# nRF52840_qfaa_var5.net
KiCad netlist of a schematic drawn in EAGLE
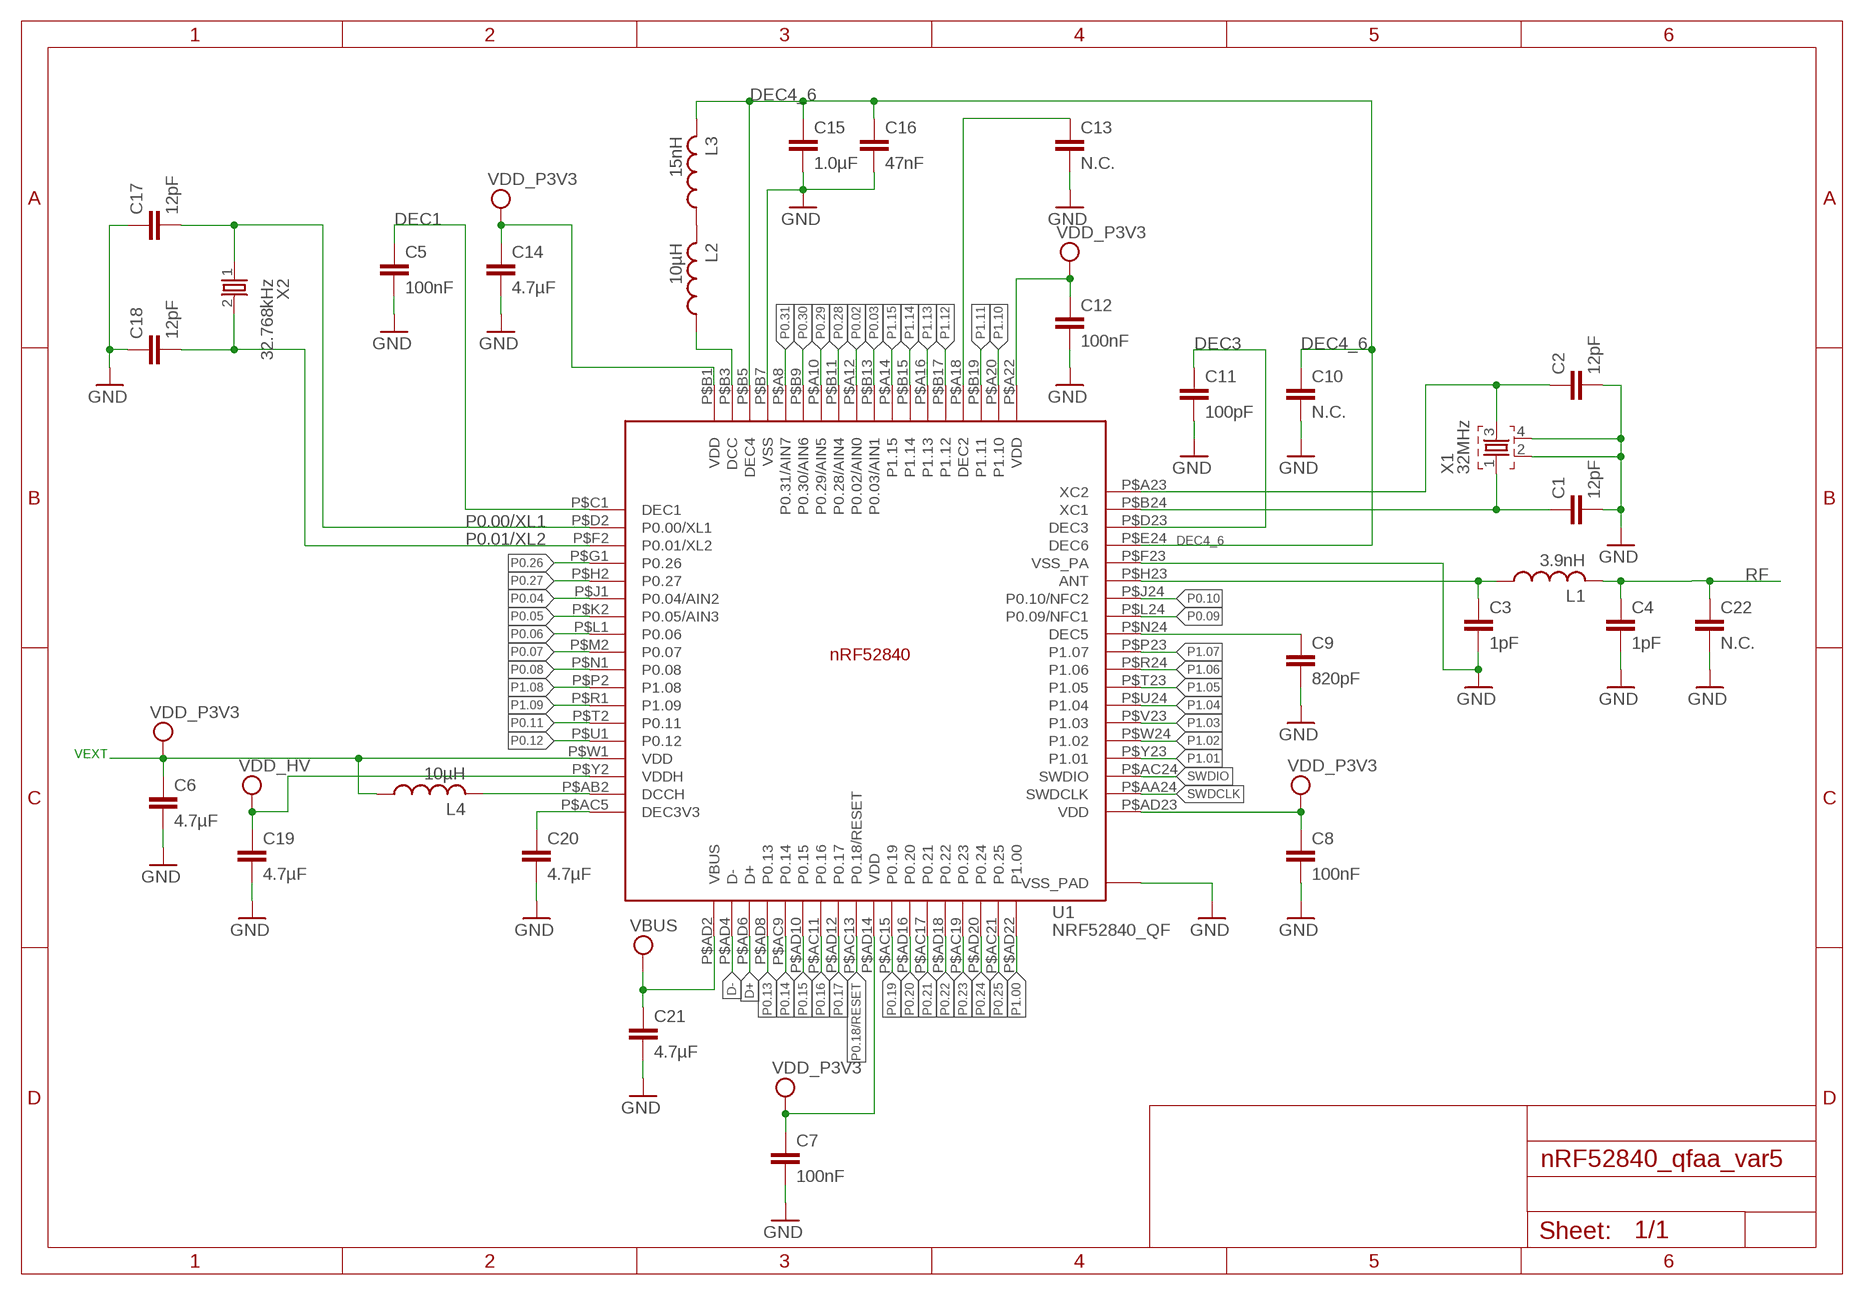
[diagram p0: schematic, sheet 1]

(export (version "E")
  (design (tool "Eeschema 10.0.6"))
  (components
    (comp (ref "C1")
      (value "12pF")
      (footprint "eagle-import:RESC0402_N")
      (libsource (lib "eagle-import") (part "CAPACITOR_0402_N"))
    )
    (comp (ref "C2")
      (value "12pF")
      (footprint "eagle-import:RESC0402_N")
      (libsource (lib "eagle-import") (part "CAPACITOR_0402_N"))
    )
    (comp (ref "C3")
      (value "1pF")
      (footprint "eagle-import:RESC0402_N")
      (libsource (lib "eagle-import") (part "CAPACITOR_0402_N"))
    )
    (comp (ref "C4")
      (value "1pF")
      (footprint "eagle-import:RESC0402_N")
      (libsource (lib "eagle-import") (part "CAPACITOR_0402_N"))
    )
    (comp (ref "C5")
      (value "100nF")
      (footprint "eagle-import:RESC0402_N")
      (libsource (lib "eagle-import") (part "CAPACITOR_0402_N"))
    )
    (comp (ref "C6")
      (value "4.7µF")
      (footprint "eagle-import:RESC0603_N")
      (libsource (lib "eagle-import") (part "CAPACITOR_0603_N"))
    )
    (comp (ref "C7")
      (value "100nF")
      (footprint "eagle-import:RESC0402_N")
      (libsource (lib "eagle-import") (part "CAPACITOR_0402_N"))
    )
    (comp (ref "C8")
      (value "100nF")
      (footprint "eagle-import:RESC0402_N")
      (libsource (lib "eagle-import") (part "CAPACITOR_0402_N"))
    )
    (comp (ref "C9")
      (value "820pF")
      (footprint "eagle-import:RESC0402_N")
      (libsource (lib "eagle-import") (part "CAPACITOR_0402_N"))
    )
    (comp (ref "C10")
      (value "N.C.")
      (footprint "eagle-import:RESC0402_N")
      (libsource (lib "eagle-import") (part "CAPACITOR_0402_N"))
    )
    (comp (ref "C11")
      (value "100pF")
      (footprint "eagle-import:RESC0402_N")
      (libsource (lib "eagle-import") (part "CAPACITOR_0402_N"))
    )
    (comp (ref "C12")
      (value "100nF")
      (footprint "eagle-import:RESC0402_N")
      (libsource (lib "eagle-import") (part "CAPACITOR_0402_N"))
    )
    (comp (ref "C13")
      (value "N.C.")
      (footprint "eagle-import:RESC0402_N")
      (libsource (lib "eagle-import") (part "CAPACITOR_0402_N"))
    )
    (comp (ref "C14")
      (value "4.7µF")
      (footprint "eagle-import:RESC0603_N")
      (libsource (lib "eagle-import") (part "CAPACITOR_0603_N"))
    )
    (comp (ref "C15")
      (value "1.0µF")
      (footprint "eagle-import:RESC0603_N")
      (libsource (lib "eagle-import") (part "CAPACITOR_0603_N"))
    )
    (comp (ref "C16")
      (value "47nF")
      (footprint "eagle-import:RESC0402_N")
      (libsource (lib "eagle-import") (part "CAPACITOR_0402_N"))
    )
    (comp (ref "C17")
      (value "12pF")
      (footprint "eagle-import:RESC0402_N")
      (libsource (lib "eagle-import") (part "CAPACITOR_0402_N"))
    )
    (comp (ref "C18")
      (value "12pF")
      (footprint "eagle-import:RESC0402_N")
      (libsource (lib "eagle-import") (part "CAPACITOR_0402_N"))
    )
    (comp (ref "C19")
      (value "4.7µF")
      (footprint "eagle-import:RESC0603_N")
      (libsource (lib "eagle-import") (part "CAPACITOR_0603_N"))
    )
    (comp (ref "C20")
      (value "4.7µF")
      (footprint "eagle-import:RESC0603_N")
      (libsource (lib "eagle-import") (part "CAPACITOR_0603_N"))
    )
    (comp (ref "C21")
      (value "4.7µF")
      (footprint "eagle-import:RESC0603_N")
      (libsource (lib "eagle-import") (part "CAPACITOR_0603_N"))
    )
    (comp (ref "C22")
      (value "N.C.")
      (footprint "eagle-import:RESC0402_N")
      (libsource (lib "eagle-import") (part "CAPACITOR_0402_N"))
    )
    (comp (ref "L1")
      (value "3.9nH")
      (footprint "eagle-import:RESC0402_N")
      (libsource (lib "eagle-import") (part "INDUCTOR_0402_N"))
    )
    (comp (ref "L2")
      (value "10µH")
      (footprint "eagle-import:RESC0603_N")
      (libsource (lib "eagle-import") (part "INDUCTOR_0603_N"))
    )
    (comp (ref "L3")
      (value "15nH")
      (footprint "eagle-import:RESC0402_N")
      (libsource (lib "eagle-import") (part "INDUCTOR_0402_N"))
    )
    (comp (ref "L4")
      (value "10µH")
      (footprint "eagle-import:RESC0603_N")
      (libsource (lib "eagle-import") (part "INDUCTOR_0603_N"))
    )
    (comp (ref "U1")
      (value "NRF52840_QF")
      (footprint "eagle-import:AQFN50P700X700X85_HS-74N")
      (libsource (lib "eagle-import") (part "NRF52840_QF"))
    )
    (comp (ref "X1")
      (value "32MHz")
      (footprint "eagle-import:BT-XTAL_2016_N")
      (libsource (lib "eagle-import") (part "XTAL_32MHZ"))
    )
    (comp (ref "X2")
      (value "32.768kHz")
      (footprint "eagle-import:XTAL_3215_N")
      (libsource (lib "eagle-import") (part "XTAL_32KHZ"))
    )
  )
  (nets
    (net (code "1") (name "/DEC1") (class "Default")
      (node (ref "C5") (pin "1") (pinfunction "1_1") (pintype "passive"))
      (node (ref "U1") (pin "P$C1") (pinfunction "DEC1_P$C1") (pintype "power_in"))
    )
    (net (code "2") (name "/DEC3") (class "Default")
      (node (ref "C11") (pin "1") (pinfunction "1_1") (pintype "passive"))
      (node (ref "U1") (pin "P$D23") (pinfunction "DEC3_P$D23") (pintype "bidirectional"))
    )
    (net (code "3") (name "/DEC4_6") (class "Default")
      (node (ref "C10") (pin "1") (pinfunction "1_1") (pintype "passive"))
      (node (ref "C15") (pin "1") (pinfunction "1_1") (pintype "passive"))
      (node (ref "C16") (pin "1") (pinfunction "1_1") (pintype "passive"))
      (node (ref "L3") (pin "2") (pinfunction "2_2") (pintype "passive"))
      (node (ref "U1") (pin "P$B5") (pinfunction "DEC4_P$B5") (pintype "power_in"))
      (node (ref "U1") (pin "P$E24") (pinfunction "DEC6_P$E24") (pintype "bidirectional"))
    )
    (net (code "4") (name "/P0.00{slash}XL1") (class "Default")
      (node (ref "C17") (pin "2") (pinfunction "2_2") (pintype "passive"))
      (node (ref "U1") (pin "P$D2") (pinfunction "P0.00/XL1_P$D2") (pintype "bidirectional"))
      (node (ref "X2") (pin "1") (pinfunction "1_1") (pintype "passive"))
    )
    (net (code "5") (name "/P0.01{slash}XL2") (class "Default")
      (node (ref "C18") (pin "2") (pinfunction "2_2") (pintype "passive"))
      (node (ref "U1") (pin "P$F2") (pinfunction "P0.01/XL2_P$F2") (pintype "bidirectional"))
      (node (ref "X2") (pin "2") (pinfunction "2_2") (pintype "passive"))
    )
    (net (code "6") (name "/RF") (class "Default")
      (node (ref "C22") (pin "1") (pinfunction "1_1") (pintype "passive"))
      (node (ref "C4") (pin "1") (pinfunction "1_1") (pintype "passive"))
      (node (ref "L1") (pin "2") (pinfunction "2_2") (pintype "passive"))
    )
    (net (code "7") (name "D+") (class "Default")
      (node (ref "U1") (pin "P$AD6") (pinfunction "D+_P$AD6") (pintype "bidirectional"))
    )
    (net (code "8") (name "D-") (class "Default")
      (node (ref "U1") (pin "P$AD4") (pinfunction "D-_P$AD4") (pintype "bidirectional"))
    )
    (net (code "9") (name "GND") (class "Default")
      (node (ref "C1") (pin "2") (pinfunction "2_2") (pintype "passive"))
      (node (ref "C10") (pin "2") (pinfunction "2_2") (pintype "passive"))
      (node (ref "C11") (pin "2") (pinfunction "2_2") (pintype "passive"))
      (node (ref "C12") (pin "2") (pinfunction "2_2") (pintype "passive"))
      (node (ref "C13") (pin "2") (pinfunction "2_2") (pintype "passive"))
      (node (ref "C14") (pin "2") (pinfunction "2_2") (pintype "passive"))
      (node (ref "C15") (pin "2") (pinfunction "2_2") (pintype "passive"))
      (node (ref "C16") (pin "2") (pinfunction "2_2") (pintype "passive"))
      (node (ref "C17") (pin "1") (pinfunction "1_1") (pintype "passive"))
      (node (ref "C18") (pin "1") (pinfunction "1_1") (pintype "passive"))
      (node (ref "C19") (pin "2") (pinfunction "2_2") (pintype "passive"))
      (node (ref "C2") (pin "2") (pinfunction "2_2") (pintype "passive"))
      (node (ref "C20") (pin "2") (pinfunction "2_2") (pintype "passive"))
      (node (ref "C21") (pin "2") (pinfunction "2_2") (pintype "passive"))
      (node (ref "C22") (pin "2") (pinfunction "2_2") (pintype "passive"))
      (node (ref "C3") (pin "2") (pinfunction "2_2") (pintype "passive"))
      (node (ref "C4") (pin "2") (pinfunction "2_2") (pintype "passive"))
      (node (ref "C5") (pin "2") (pinfunction "2_2") (pintype "passive"))
      (node (ref "C6") (pin "2") (pinfunction "2_2") (pintype "passive"))
      (node (ref "C7") (pin "2") (pinfunction "2_2") (pintype "passive"))
      (node (ref "C8") (pin "2") (pinfunction "2_2") (pintype "passive"))
      (node (ref "C9") (pin "2") (pinfunction "2_2") (pintype "passive"))
      (node (ref "U1") (pin "P$74") (pinfunction "VSS_PAD_P$74") (pintype "bidirectional"))
      (node (ref "U1") (pin "P$75") (pinfunction "VSS_PAD_P$75") (pintype "bidirectional"))
      (node (ref "U1") (pin "P$76") (pinfunction "VSS_PAD_P$76") (pintype "bidirectional"))
      (node (ref "U1") (pin "P$77") (pinfunction "VSS_PAD_P$77") (pintype "bidirectional"))
      (node (ref "U1") (pin "P$78") (pinfunction "VSS_PAD_P$78") (pintype "bidirectional"))
      (node (ref "U1") (pin "P$79") (pinfunction "VSS_PAD_P$79") (pintype "bidirectional"))
      (node (ref "U1") (pin "P$80") (pinfunction "VSS_PAD_P$80") (pintype "bidirectional"))
      (node (ref "U1") (pin "P$81") (pinfunction "VSS_PAD_P$81") (pintype "bidirectional"))
      (node (ref "U1") (pin "P$82") (pinfunction "VSS_PAD_P$82") (pintype "bidirectional"))
      (node (ref "U1") (pin "P$83") (pinfunction "VSS_PAD_P$83") (pintype "bidirectional"))
      (node (ref "U1") (pin "P$84") (pinfunction "VSS_PAD_P$84") (pintype "bidirectional"))
      (node (ref "U1") (pin "P$85") (pinfunction "VSS_PAD_P$85") (pintype "bidirectional"))
      (node (ref "U1") (pin "P$86") (pinfunction "VSS_PAD_P$86") (pintype "bidirectional"))
      (node (ref "U1") (pin "P$87") (pinfunction "VSS_PAD_P$87") (pintype "bidirectional"))
      (node (ref "U1") (pin "P$88") (pinfunction "VSS_PAD_P$88") (pintype "bidirectional"))
      (node (ref "U1") (pin "P$89") (pinfunction "VSS_PAD_P$89") (pintype "bidirectional"))
      (node (ref "U1") (pin "P$90") (pinfunction "VSS_PAD_P$90") (pintype "bidirectional"))
      (node (ref "U1") (pin "P$B7") (pinfunction "VSS_P$B7") (pintype "power_in"))
      (node (ref "U1") (pin "P$F23") (pinfunction "VSS_PA_P$F23") (pintype "bidirectional"))
      (node (ref "X1") (pin "2") (pinfunction "2_2") (pintype "passive"))
      (node (ref "X1") (pin "4") (pinfunction "4_4") (pintype "passive"))
    )
    (net (code "10") (name "Net-(L2-Pad2)") (class "Default")
      (node (ref "L2") (pin "2") (pinfunction "2_2") (pintype "passive"))
      (node (ref "L3") (pin "1") (pinfunction "1_1") (pintype "passive"))
    )
    (net (code "11") (name "Net-(U1-ANT)") (class "Default")
      (node (ref "C3") (pin "1") (pinfunction "1_1") (pintype "passive"))
      (node (ref "L1") (pin "1") (pinfunction "1_1") (pintype "passive"))
      (node (ref "U1") (pin "P$H23") (pinfunction "ANT_P$H23") (pintype "bidirectional"))
    )
    (net (code "12") (name "Net-(U1-DCC)") (class "Default")
      (node (ref "L2") (pin "1") (pinfunction "1_1") (pintype "passive"))
      (node (ref "U1") (pin "P$B3") (pinfunction "DCC_P$B3") (pintype "output"))
    )
    (net (code "13") (name "Net-(U1-DCCH)") (class "Default")
      (node (ref "L4") (pin "2") (pinfunction "2_2") (pintype "passive"))
      (node (ref "U1") (pin "P$AB2") (pinfunction "DCCH_P$AB2") (pintype "bidirectional"))
    )
    (net (code "14") (name "Net-(U1-DEC2)") (class "Default")
      (node (ref "C13") (pin "1") (pinfunction "1_1") (pintype "passive"))
      (node (ref "U1") (pin "P$A18") (pinfunction "DEC2_P$A18") (pintype "bidirectional"))
    )
    (net (code "15") (name "Net-(U1-DEC3V3)") (class "Default")
      (node (ref "C20") (pin "1") (pinfunction "1_1") (pintype "passive"))
      (node (ref "U1") (pin "P$AC5") (pinfunction "DEC3V3_P$AC5") (pintype "bidirectional"))
    )
    (net (code "16") (name "Net-(U1-DEC5)") (class "Default")
      (node (ref "C9") (pin "1") (pinfunction "1_1") (pintype "passive"))
      (node (ref "U1") (pin "P$N24") (pinfunction "DEC5_P$N24") (pintype "bidirectional"))
    )
    (net (code "17") (name "Net-(U1-XC1)") (class "Default")
      (node (ref "C1") (pin "1") (pinfunction "1_1") (pintype "passive"))
      (node (ref "U1") (pin "P$B24") (pinfunction "XC1_P$B24") (pintype "input"))
      (node (ref "X1") (pin "1") (pinfunction "1_1") (pintype "passive"))
    )
    (net (code "18") (name "Net-(U1-XC2)") (class "Default")
      (node (ref "C2") (pin "1") (pinfunction "1_1") (pintype "passive"))
      (node (ref "U1") (pin "P$A23") (pinfunction "XC2_P$A23") (pintype "output"))
      (node (ref "X1") (pin "3") (pinfunction "3_3") (pintype "passive"))
    )
    (net (code "19") (name "P0.02") (class "Default")
      (node (ref "U1") (pin "P$A12") (pinfunction "P0.02/AIN0_P$A12") (pintype "bidirectional"))
    )
    (net (code "20") (name "P0.03") (class "Default")
      (node (ref "U1") (pin "P$B13") (pinfunction "P0.03/AIN1_P$B13") (pintype "bidirectional"))
    )
    (net (code "21") (name "P0.04") (class "Default")
      (node (ref "U1") (pin "P$J1") (pinfunction "P0.04/AIN2_P$J1") (pintype "bidirectional"))
    )
    (net (code "22") (name "P0.05") (class "Default")
      (node (ref "U1") (pin "P$K2") (pinfunction "P0.05/AIN3_P$K2") (pintype "bidirectional"))
    )
    (net (code "23") (name "P0.06") (class "Default")
      (node (ref "U1") (pin "P$L1") (pinfunction "P0.06_P$L1") (pintype "bidirectional"))
    )
    (net (code "24") (name "P0.07") (class "Default")
      (node (ref "U1") (pin "P$M2") (pinfunction "P0.07_P$M2") (pintype "bidirectional"))
    )
    (net (code "25") (name "P0.08") (class "Default")
      (node (ref "U1") (pin "P$N1") (pinfunction "P0.08_P$N1") (pintype "bidirectional"))
    )
    (net (code "26") (name "P0.09") (class "Default")
      (node (ref "U1") (pin "P$L24") (pinfunction "P0.09/NFC1_P$L24") (pintype "bidirectional"))
    )
    (net (code "27") (name "P0.10") (class "Default")
      (node (ref "U1") (pin "P$J24") (pinfunction "P0.10/NFC2_P$J24") (pintype "bidirectional"))
    )
    (net (code "28") (name "P0.11") (class "Default")
      (node (ref "U1") (pin "P$T2") (pinfunction "P0.11_P$T2") (pintype "bidirectional"))
    )
    (net (code "29") (name "P0.12") (class "Default")
      (node (ref "U1") (pin "P$U1") (pinfunction "P0.12_P$U1") (pintype "bidirectional"))
    )
    (net (code "30") (name "P0.13") (class "Default")
      (node (ref "U1") (pin "P$AD8") (pinfunction "P0.13_P$AD8") (pintype "bidirectional"))
    )
    (net (code "31") (name "P0.14") (class "Default")
      (node (ref "U1") (pin "P$AC9") (pinfunction "P0.14_P$AC9") (pintype "bidirectional"))
    )
    (net (code "32") (name "P0.15") (class "Default")
      (node (ref "U1") (pin "P$AD10") (pinfunction "P0.15_P$AD10") (pintype "bidirectional"))
    )
    (net (code "33") (name "P0.16") (class "Default")
      (node (ref "U1") (pin "P$AC11") (pinfunction "P0.16_P$AC11") (pintype "bidirectional"))
    )
    (net (code "34") (name "P0.17") (class "Default")
      (node (ref "U1") (pin "P$AD12") (pinfunction "P0.17_P$AD12") (pintype "bidirectional"))
    )
    (net (code "35") (name "P0.18{slash}RESET") (class "Default")
      (node (ref "U1") (pin "P$AC13") (pinfunction "P0.18/RESET_P$AC13") (pintype "bidirectional"))
    )
    (net (code "36") (name "P0.19") (class "Default")
      (node (ref "U1") (pin "P$AC15") (pinfunction "P0.19_P$AC15") (pintype "bidirectional"))
    )
    (net (code "37") (name "P0.20") (class "Default")
      (node (ref "U1") (pin "P$AD16") (pinfunction "P0.20_P$AD16") (pintype "bidirectional"))
    )
    (net (code "38") (name "P0.21") (class "Default")
      (node (ref "U1") (pin "P$AC17") (pinfunction "P0.21_P$AC17") (pintype "bidirectional"))
    )
    (net (code "39") (name "P0.22") (class "Default")
      (node (ref "U1") (pin "P$AD18") (pinfunction "P0.22_P$AD18") (pintype "bidirectional"))
    )
    (net (code "40") (name "P0.23") (class "Default")
      (node (ref "U1") (pin "P$AC19") (pinfunction "P0.23_P$AC19") (pintype "bidirectional"))
    )
    (net (code "41") (name "P0.24") (class "Default")
      (node (ref "U1") (pin "P$AD20") (pinfunction "P0.24_P$AD20") (pintype "bidirectional"))
    )
    (net (code "42") (name "P0.25") (class "Default")
      (node (ref "U1") (pin "P$AC21") (pinfunction "P0.25_P$AC21") (pintype "bidirectional"))
    )
    (net (code "43") (name "P0.26") (class "Default")
      (node (ref "U1") (pin "P$G1") (pinfunction "P0.26_P$G1") (pintype "bidirectional"))
    )
    (net (code "44") (name "P0.27") (class "Default")
      (node (ref "U1") (pin "P$H2") (pinfunction "P0.27_P$H2") (pintype "bidirectional"))
    )
    (net (code "45") (name "P0.28") (class "Default")
      (node (ref "U1") (pin "P$B11") (pinfunction "P0.28/AIN4_P$B11") (pintype "bidirectional"))
    )
    (net (code "46") (name "P0.29") (class "Default")
      (node (ref "U1") (pin "P$A10") (pinfunction "P0.29/AIN5_P$A10") (pintype "bidirectional"))
    )
    (net (code "47") (name "P0.30") (class "Default")
      (node (ref "U1") (pin "P$B9") (pinfunction "P0.30/AIN6_P$B9") (pintype "bidirectional"))
    )
    (net (code "48") (name "P0.31") (class "Default")
      (node (ref "U1") (pin "P$A8") (pinfunction "P0.31/AIN7_P$A8") (pintype "bidirectional"))
    )
    (net (code "49") (name "P1.00") (class "Default")
      (node (ref "U1") (pin "P$AD22") (pinfunction "P1.00_P$AD22") (pintype "bidirectional"))
    )
    (net (code "50") (name "P1.01") (class "Default")
      (node (ref "U1") (pin "P$Y23") (pinfunction "P1.01_P$Y23") (pintype "bidirectional"))
    )
    (net (code "51") (name "P1.02") (class "Default")
      (node (ref "U1") (pin "P$W24") (pinfunction "P1.02_P$W24") (pintype "bidirectional"))
    )
    (net (code "52") (name "P1.03") (class "Default")
      (node (ref "U1") (pin "P$V23") (pinfunction "P1.03_P$V23") (pintype "bidirectional"))
    )
    (net (code "53") (name "P1.04") (class "Default")
      (node (ref "U1") (pin "P$U24") (pinfunction "P1.04_P$U24") (pintype "bidirectional"))
    )
    (net (code "54") (name "P1.05") (class "Default")
      (node (ref "U1") (pin "P$T23") (pinfunction "P1.05_P$T23") (pintype "bidirectional"))
    )
    (net (code "55") (name "P1.06") (class "Default")
      (node (ref "U1") (pin "P$R24") (pinfunction "P1.06_P$R24") (pintype "bidirectional"))
    )
    (net (code "56") (name "P1.07") (class "Default")
      (node (ref "U1") (pin "P$P23") (pinfunction "P1.07_P$P23") (pintype "bidirectional"))
    )
    (net (code "57") (name "P1.08") (class "Default")
      (node (ref "U1") (pin "P$P2") (pinfunction "P1.08_P$P2") (pintype "bidirectional"))
    )
    (net (code "58") (name "P1.09") (class "Default")
      (node (ref "U1") (pin "P$R1") (pinfunction "P1.09_P$R1") (pintype "bidirectional"))
    )
    (net (code "59") (name "P1.10") (class "Default")
      (node (ref "U1") (pin "P$A20") (pinfunction "P1.10_P$A20") (pintype "bidirectional"))
    )
    (net (code "60") (name "P1.11") (class "Default")
      (node (ref "U1") (pin "P$B19") (pinfunction "P1.11_P$B19") (pintype "bidirectional"))
    )
    (net (code "61") (name "P1.12") (class "Default")
      (node (ref "U1") (pin "P$B17") (pinfunction "P1.12_P$B17") (pintype "bidirectional"))
    )
    (net (code "62") (name "P1.13") (class "Default")
      (node (ref "U1") (pin "P$A16") (pinfunction "P1.13_P$A16") (pintype "bidirectional"))
    )
    (net (code "63") (name "P1.14") (class "Default")
      (node (ref "U1") (pin "P$B15") (pinfunction "P1.14_P$B15") (pintype "bidirectional"))
    )
    (net (code "64") (name "P1.15") (class "Default")
      (node (ref "U1") (pin "P$A14") (pinfunction "P1.15_P$A14") (pintype "bidirectional"))
    )
    (net (code "65") (name "SWDCLK") (class "Default")
      (node (ref "U1") (pin "P$AA24") (pinfunction "SWDCLK_P$AA24") (pintype "input"))
    )
    (net (code "66") (name "SWDIO") (class "Default")
      (node (ref "U1") (pin "P$AC24") (pinfunction "SWDIO_P$AC24") (pintype "bidirectional"))
    )
    (net (code "67") (name "VBUS") (class "Default")
      (node (ref "C21") (pin "1") (pinfunction "1_1") (pintype "passive"))
      (node (ref "U1") (pin "P$AD2") (pinfunction "VBUS_P$AD2") (pintype "power_in"))
    )
    (net (code "68") (name "VDD_HV") (class "Default")
      (node (ref "C19") (pin "1") (pinfunction "1_1") (pintype "passive"))
      (node (ref "U1") (pin "P$Y2") (pinfunction "VDDH_P$Y2") (pintype "power_in"))
    )
    (net (code "69") (name "VDD_P3V3") (class "Default")
      (node (ref "C12") (pin "1") (pinfunction "1_1") (pintype "passive"))
      (node (ref "C14") (pin "1") (pinfunction "1_1") (pintype "passive"))
      (node (ref "C6") (pin "1") (pinfunction "1_1") (pintype "passive"))
      (node (ref "C7") (pin "1") (pinfunction "1_1") (pintype "passive"))
      (node (ref "C8") (pin "1") (pinfunction "1_1") (pintype "passive"))
      (node (ref "L4") (pin "1") (pinfunction "1_1") (pintype "passive"))
      (node (ref "U1") (pin "P$A22") (pinfunction "VDD_P$A22") (pintype "power_in"))
      (node (ref "U1") (pin "P$AD14") (pinfunction "VDD_P$AD14") (pintype "power_in"))
      (node (ref "U1") (pin "P$AD23") (pinfunction "VDD_P$AD23") (pintype "power_in"))
      (node (ref "U1") (pin "P$B1") (pinfunction "VDD_P$B1") (pintype "power_in"))
      (node (ref "U1") (pin "P$W1") (pinfunction "VDD_P$W1") (pintype "power_in"))
    )
  )
)
